# TiltyDuo.net
KiCad netlist of a schematic drawn in EAGLE
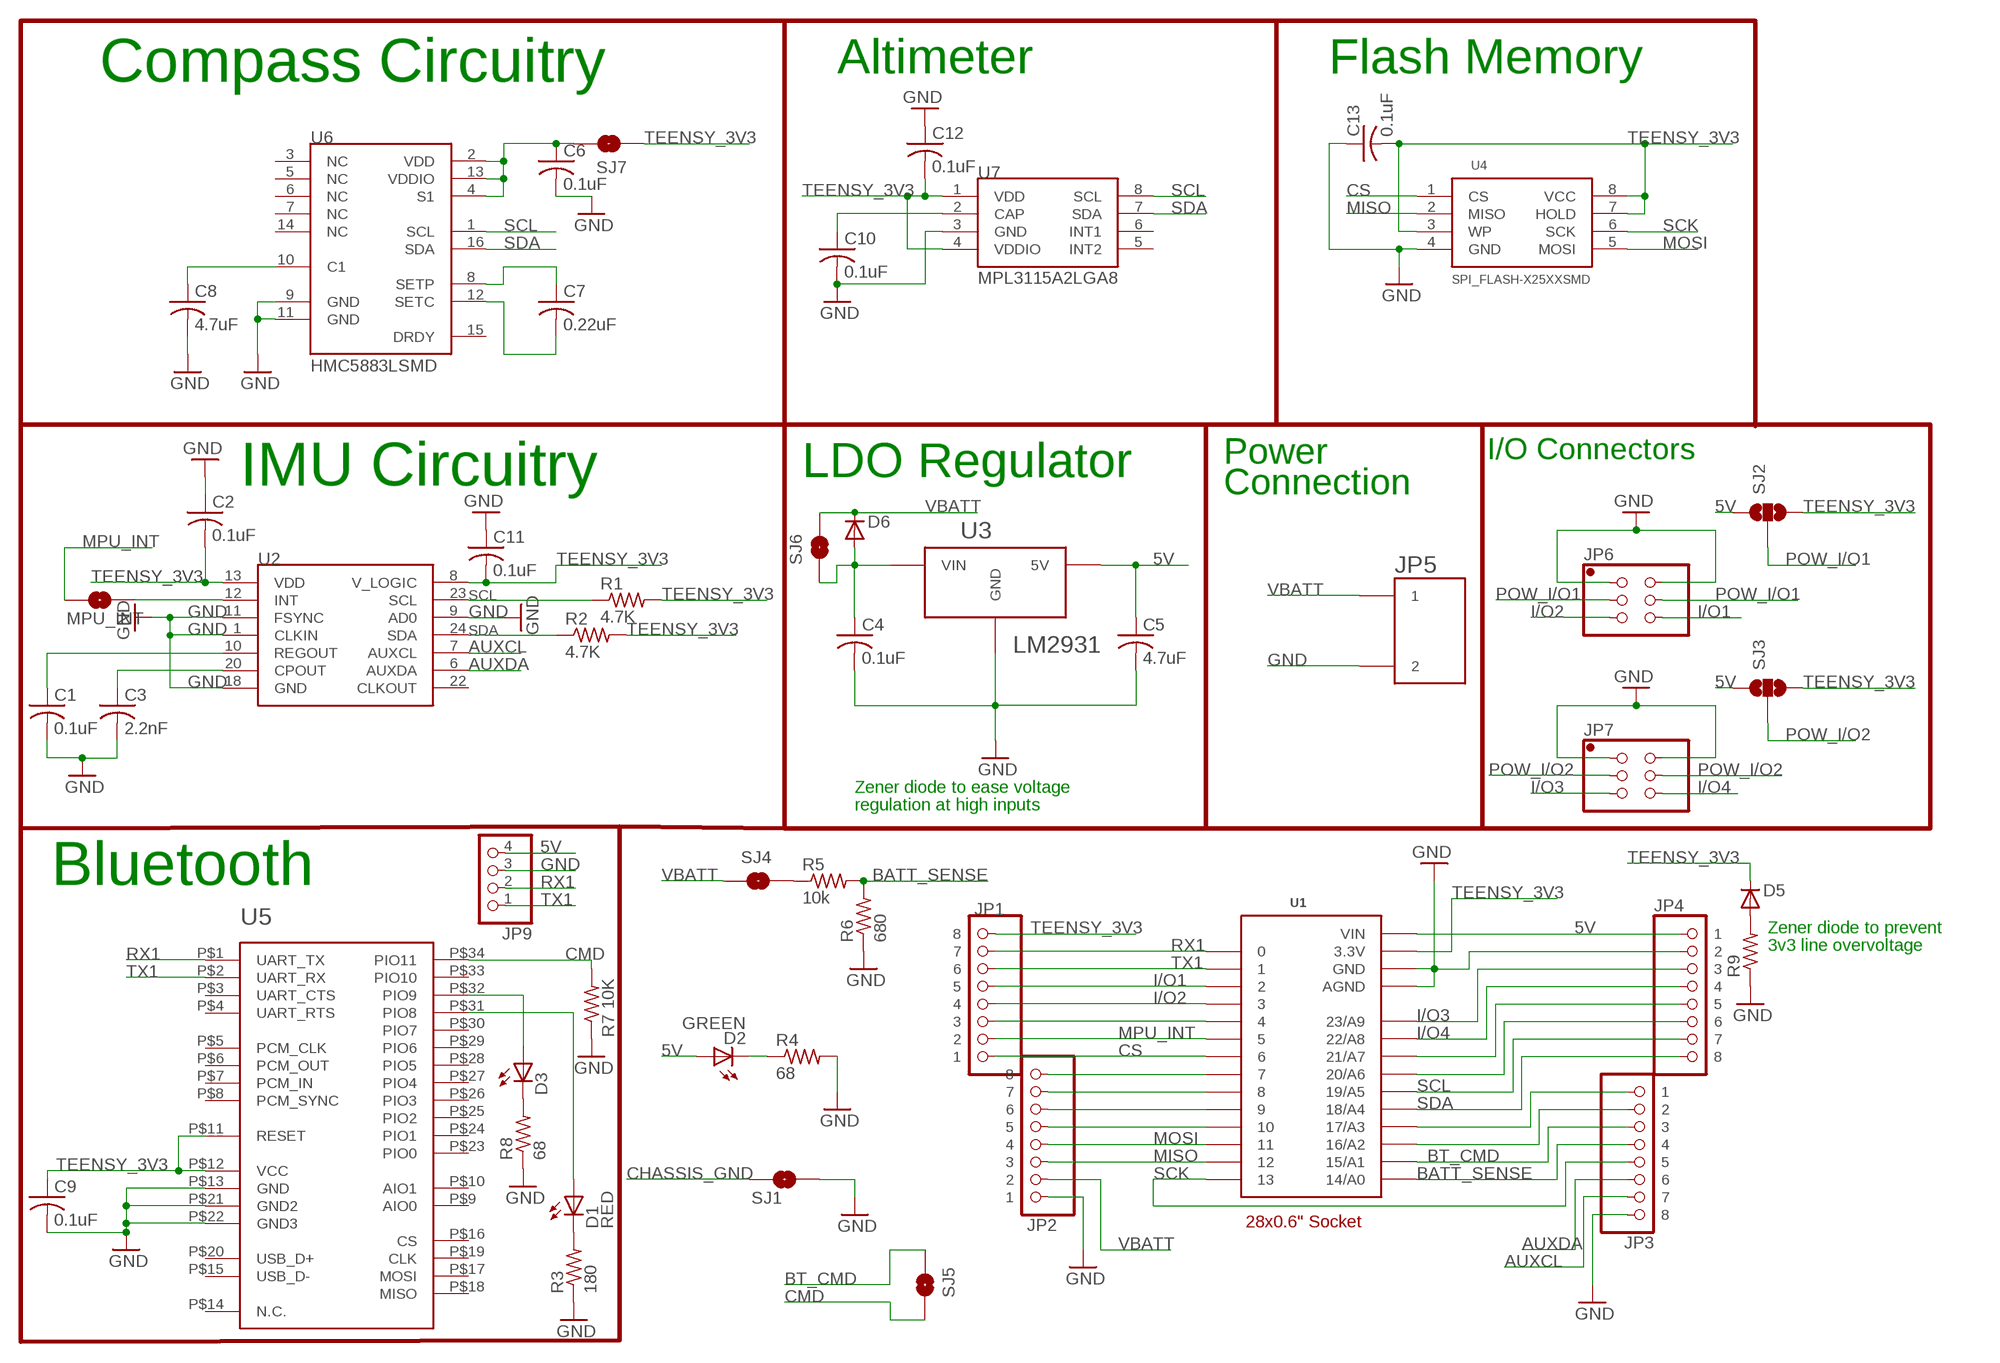
[diagram p0: schematic, sheet 1]

(export (version "E")
  (design (tool "Eeschema 10.0.6"))
  (components
    (comp (ref "C1")
      (value "0.1uF")
      (footprint "eagle-import:C0603")
      (libsource (lib "eagle-import") (part "C-USC0603"))
    )
    (comp (ref "C2")
      (value "0.1uF")
      (footprint "eagle-import:C0603")
      (libsource (lib "eagle-import") (part "C-USC0603"))
    )
    (comp (ref "C3")
      (value "2.2nF")
      (footprint "eagle-import:C0603")
      (libsource (lib "eagle-import") (part "C-USC0603"))
    )
    (comp (ref "C4")
      (value "0.1uF")
      (footprint "eagle-import:C0603")
      (libsource (lib "eagle-import") (part "C-USC0603"))
    )
    (comp (ref "C5")
      (value "4.7uF")
      (footprint "eagle-import:C0603")
      (libsource (lib "eagle-import") (part "C-USC0603"))
    )
    (comp (ref "C6")
      (value "0.1uF")
      (footprint "eagle-import:C0603")
      (libsource (lib "eagle-import") (part "C-USC0603"))
    )
    (comp (ref "C7")
      (value "0.22uF")
      (footprint "eagle-import:C0603")
      (libsource (lib "eagle-import") (part "C-USC0603"))
    )
    (comp (ref "C8")
      (value "4.7uF")
      (footprint "eagle-import:C0603")
      (libsource (lib "eagle-import") (part "C-USC0603"))
    )
    (comp (ref "C9")
      (value "0.1uF")
      (footprint "eagle-import:C0603")
      (libsource (lib "eagle-import") (part "C-USC0603"))
    )
    (comp (ref "C10")
      (value "0.1uF")
      (footprint "eagle-import:C0603")
      (libsource (lib "eagle-import") (part "C-USC0603"))
    )
    (comp (ref "C11")
      (value "0.1uF")
      (footprint "eagle-import:C0603")
      (libsource (lib "eagle-import") (part "C-USC0603"))
    )
    (comp (ref "C12")
      (value "0.1uF")
      (footprint "eagle-import:C0603")
      (libsource (lib "eagle-import") (part "C-USC0603"))
    )
    (comp (ref "C13")
      (value "0.1uF")
      (footprint "eagle-import:C0603")
      (libsource (lib "eagle-import") (part "C-USC0603"))
    )
    (comp (ref "D1")
      (value "RED")
      (footprint "eagle-import:LED-0805")
      (libsource (lib "eagle-import") (part "LED-GREENLED-0805_NO_SILK"))
    )
    (comp (ref "D2")
      (value "GREEN")
      (footprint "eagle-import:LED-0805")
      (libsource (lib "eagle-import") (part "LED-GREENLED-0805_NO_SILK"))
    )
    (comp (ref "D3")
      (value "YELLOW")
      (footprint "eagle-import:LED-0805")
      (libsource (lib "eagle-import") (part "LED-GREENLED-0805_NO_SILK"))
    )
    (comp (ref "D5")
      (value "DIODESOT23")
      (footprint "eagle-import:SOT23-3")
      (fields (field (name "PART#") "BZX84C3V3LT1GOSCT-ND"))
      (libsource (lib "eagle-import") (part "DIODESOT23"))
    )
    (comp (ref "D6")
      (value "DIODE-DO214AA")
      (footprint "eagle-import:DO214AA")
      (libsource (lib "eagle-import") (part "DIODE-DO214AA"))
    )
    (comp (ref "JP1")
      (value "8-PIN_HEADER")
      (footprint "eagle-import:8-PIN_RECEPTACLE_LOCK_NO-SS")
      (libsource (lib "eagle-import") (part "8-PIN_HEADER"))
    )
    (comp (ref "JP2")
      (value "8-PIN_HEADER")
      (footprint "eagle-import:8-PIN_RECEPTACLE_LOCK_NO-SS")
      (libsource (lib "eagle-import") (part "8-PIN_HEADER"))
    )
    (comp (ref "JP3")
      (value "8-PIN_HEADER")
      (footprint "eagle-import:8-PIN_RECEPTACLE_LOCK_NO-SS")
      (libsource (lib "eagle-import") (part "8-PIN_HEADER"))
    )
    (comp (ref "JP4")
      (value "8-PIN_HEADER")
      (footprint "eagle-import:8-PIN_RECEPTACLE_LOCK_NO-SS")
      (libsource (lib "eagle-import") (part "8-PIN_HEADER"))
    )
    (comp (ref "JP5")
      (value "2-POS_SMD_TERM_BLOCK")
      (footprint "eagle-import:2-POS_SMD_TERMINAL_BLOCK")
      (fields (field (name "PART#") "277-2337-1-ND"))
      (libsource (lib "eagle-import") (part "2-POS_SMD_TERM_BLOCK"))
    )
    (comp (ref "JP6")
      (value "PINHD-2X32X03_NO_SS_LOCK")
      (footprint "eagle-import:2X03_NO_SS_LOCK")
      (libsource (lib "eagle-import") (part "PINHD-2X32X03_NO_SS_LOCK"))
    )
    (comp (ref "JP7")
      (value "PINHD-2X32X03_NO_SS_LOCK")
      (footprint "eagle-import:2X03_NO_SS_LOCK")
      (libsource (lib "eagle-import") (part "PINHD-2X32X03_NO_SS_LOCK"))
    )
    (comp (ref "JP9")
      (value "PINHD-1X41X04_NO_SS_LOCKING")
      (footprint "eagle-import:1X04_NO_SS_LOCKING")
      (libsource (lib "eagle-import") (part "PINHD-1X41X04_NO_SS_LOCKING"))
    )
    (comp (ref "MPU_INT")
      (value "SOLDERJUMPERNO")
      (footprint "eagle-import:SJ_2S-NO")
      (libsource (lib "eagle-import") (part "SOLDERJUMPERNO"))
    )
    (comp (ref "R1")
      (value "4.7K")
      (footprint "eagle-import:R0603")
      (libsource (lib "eagle-import") (part "R-US_R0603"))
    )
    (comp (ref "R2")
      (value "4.7K")
      (footprint "eagle-import:R0603")
      (libsource (lib "eagle-import") (part "R-US_R0603"))
    )
    (comp (ref "R3")
      (value "180")
      (footprint "eagle-import:R0603")
      (libsource (lib "eagle-import") (part "R-US_R0603"))
    )
    (comp (ref "R4")
      (value "68")
      (footprint "eagle-import:R0603")
      (libsource (lib "eagle-import") (part "R-US_R0603"))
    )
    (comp (ref "R5")
      (value "10k")
      (footprint "eagle-import:R0603")
      (libsource (lib "eagle-import") (part "R-US_R0603"))
    )
    (comp (ref "R6")
      (value "680")
      (footprint "eagle-import:R0603")
      (libsource (lib "eagle-import") (part "R-US_R0603"))
    )
    (comp (ref "R7")
      (value "10K")
      (footprint "eagle-import:R0603")
      (libsource (lib "eagle-import") (part "R-US_R0603"))
    )
    (comp (ref "R8")
      (value "68")
      (footprint "eagle-import:R0603")
      (libsource (lib "eagle-import") (part "R-US_R0603"))
    )
    (comp (ref "R9")
      (value "R-US_R0603")
      (footprint "eagle-import:R0603")
      (libsource (lib "eagle-import") (part "R-US_R0603"))
    )
    (comp (ref "SJ1")
      (value "SOLDERJUMPERNO")
      (footprint "eagle-import:SJ_2S-NO")
      (libsource (lib "eagle-import") (part "SOLDERJUMPERNO"))
    )
    (comp (ref "SJ2")
      (value "SOLDERJUMPER_2WAYPASTE1&2")
      (footprint "eagle-import:SJ_3_PASTE1&2")
      (libsource (lib "eagle-import") (part "SOLDERJUMPER_2WAYPASTE1&2"))
    )
    (comp (ref "SJ3")
      (value "SOLDERJUMPER_2WAYS")
      (footprint "eagle-import:SJ_3")
      (libsource (lib "eagle-import") (part "SOLDERJUMPER_2WAYS"))
    )
    (comp (ref "SJ4")
      (value "SOLDERJUMPERTRACE")
      (footprint "eagle-import:SJ_2S-TRACE")
      (libsource (lib "eagle-import") (part "SOLDERJUMPERTRACE"))
    )
    (comp (ref "SJ5")
      (value "SOLDERJUMPERTRACE")
      (footprint "eagle-import:SJ_2S-TRACE")
      (libsource (lib "eagle-import") (part "SOLDERJUMPERTRACE"))
    )
    (comp (ref "SJ6")
      (value "SOLDERJUMPERTRACE")
      (footprint "eagle-import:SJ_2S-TRACE")
      (libsource (lib "eagle-import") (part "SOLDERJUMPERTRACE"))
    )
    (comp (ref "SJ7")
      (value "SOLDERJUMPERTRACE")
      (footprint "eagle-import:SJ_2S-TRACE")
      (libsource (lib "eagle-import") (part "SOLDERJUMPERTRACE"))
    )
    (comp (ref "U1")
      (value "TEENSY_3.0_OUTER-PINS28-DIP_SOCKET")
      (footprint "eagle-import:28-DIP")
      (fields (field (name "PART#") "AE10004-ND"))
      (libsource (lib "eagle-import") (part "TEENSY_3.0_OUTER-PINS28-DIP_SOCKET"))
    )
    (comp (ref "U2")
      (value "MPU-6050")
      (footprint "eagle-import:QFN-24")
      (libsource (lib "eagle-import") (part "MPU-6050"))
    )
    (comp (ref "U3")
      (value "LM2931")
      (footprint "eagle-import:TO263")
      (libsource (lib "eagle-import") (part "LM2931"))
    )
    (comp (ref "U4")
      (value "SPI_FLASH-X25XXSMD")
      (footprint "eagle-import:SO08")
      (fields (field (name "PART#") "S25FL204K0TMFI043"))
      (libsource (lib "eagle-import") (part "SPI_FLASH-X25XXSMD"))
    )
    (comp (ref "U5")
      (value "HC-09_BREAKOUT")
      (footprint "eagle-import:HC-09_BREAKOUT")
      (libsource (lib "eagle-import") (part "HC-09_BREAKOUT"))
    )
    (comp (ref "U6")
      (value "HMC5883LSMD")
      (footprint "eagle-import:16LPCC")
      (libsource (lib "eagle-import") (part "HMC5883LSMD"))
    )
    (comp (ref "U7")
      (value "MPL3115A2LGA8")
      (footprint "eagle-import:LGA8")
      (libsource (lib "eagle-import") (part "MPL3115A2LGA8"))
    )
  )
  (nets
    (net (code "1") (name "/5V") (class "Default")
      (node (ref "C5") (pin "1") (pinfunction "1_1") (pintype "passive"))
      (node (ref "D2") (pin "1") (pinfunction "A_1") (pintype "passive"))
      (node (ref "JP4") (pin "P$1") (pinfunction "1_P$1") (pintype "passive"))
      (node (ref "JP9") (pin "4") (pinfunction "4_4") (pintype "passive"))
      (node (ref "SJ2") (pin "1") (pinfunction "1_1") (pintype "passive"))
      (node (ref "SJ3") (pin "1") (pinfunction "1_1") (pintype "passive"))
      (node (ref "U1") (pin "P$15") (pinfunction "VIN_P$15") (pintype "power_in"))
      (node (ref "U3") (pin "P$3") (pinfunction "5V_P$3") (pintype "bidirectional"))
    )
    (net (code "2") (name "/AUXCL") (class "Default")
      (node (ref "JP3") (pin "P$7") (pinfunction "7_P$7") (pintype "passive"))
      (node (ref "U2") (pin "7") (pinfunction "AUXCL_7") (pintype "bidirectional"))
    )
    (net (code "3") (name "/AUXDA") (class "Default")
      (node (ref "JP3") (pin "P$6") (pinfunction "6_P$6") (pintype "passive"))
      (node (ref "U2") (pin "6") (pinfunction "AUXDA_6") (pintype "bidirectional"))
    )
    (net (code "4") (name "/BATT_SENSE") (class "Default")
      (node (ref "JP3") (pin "P$4") (pinfunction "4_P$4") (pintype "passive"))
      (node (ref "R5") (pin "2") (pinfunction "2_2") (pintype "passive"))
      (node (ref "R6") (pin "2") (pinfunction "2_2") (pintype "passive"))
      (node (ref "U1") (pin "P$27") (pinfunction "14/A0_P$27") (pintype "bidirectional"))
    )
    (net (code "5") (name "/BT_CMD") (class "Default")
      (node (ref "JP3") (pin "P$3") (pinfunction "3_P$3") (pintype "passive"))
      (node (ref "SJ5") (pin "1") (pinfunction "1_1") (pintype "passive"))
      (node (ref "U1") (pin "P$26") (pinfunction "15/A1_P$26") (pintype "bidirectional"))
    )
    (net (code "6") (name "/CHASSIS_GND") (class "Default")
      (node (ref "SJ1") (pin "1") (pinfunction "1_1") (pintype "passive"))
    )
    (net (code "7") (name "/CMD") (class "Default")
      (node (ref "R7") (pin "2") (pinfunction "2_2") (pintype "passive"))
      (node (ref "SJ5") (pin "2") (pinfunction "2_2") (pintype "passive"))
      (node (ref "U5") (pin "P$34") (pinfunction "PIO11_P$34") (pintype "bidirectional"))
    )
    (net (code "8") (name "/CS") (class "Default")
      (node (ref "JP1") (pin "P$1") (pinfunction "1_P$1") (pintype "passive"))
      (node (ref "U1") (pin "P$8") (pinfunction "6_P$8") (pintype "bidirectional"))
      (node (ref "U4") (pin "1") (pinfunction "CS_1") (pintype "bidirectional"))
    )
    (net (code "9") (name "/I{slash}O1") (class "Default")
      (node (ref "JP1") (pin "P$5") (pinfunction "5_P$5") (pintype "passive"))
      (node (ref "JP6") (pin "6") (pinfunction "6_6") (pintype "passive"))
      (node (ref "U1") (pin "P$4") (pinfunction "2_P$4") (pintype "bidirectional"))
    )
    (net (code "10") (name "/I{slash}O2") (class "Default")
      (node (ref "JP1") (pin "P$4") (pinfunction "4_P$4") (pintype "passive"))
      (node (ref "JP6") (pin "5") (pinfunction "5_5") (pintype "passive"))
      (node (ref "U1") (pin "P$5") (pinfunction "3_P$5") (pintype "bidirectional"))
    )
    (net (code "11") (name "/I{slash}O3") (class "Default")
      (node (ref "JP4") (pin "P$3") (pinfunction "3_P$3") (pintype "passive"))
      (node (ref "JP7") (pin "5") (pinfunction "5_5") (pintype "passive"))
      (node (ref "U1") (pin "P$18") (pinfunction "23/A9_P$18") (pintype "bidirectional"))
    )
    (net (code "12") (name "/I{slash}O4") (class "Default")
      (node (ref "JP4") (pin "P$4") (pinfunction "4_P$4") (pintype "passive"))
      (node (ref "JP7") (pin "6") (pinfunction "6_6") (pintype "passive"))
      (node (ref "U1") (pin "P$19") (pinfunction "22/A8_P$19") (pintype "bidirectional"))
    )
    (net (code "13") (name "/MISO") (class "Default")
      (node (ref "JP2") (pin "P$3") (pinfunction "3_P$3") (pintype "passive"))
      (node (ref "U1") (pin "P$14") (pinfunction "12_P$14") (pintype "bidirectional"))
      (node (ref "U4") (pin "2") (pinfunction "MISO_2") (pintype "bidirectional"))
    )
    (net (code "14") (name "/MOSI") (class "Default")
      (node (ref "JP2") (pin "P$4") (pinfunction "4_P$4") (pintype "passive"))
      (node (ref "U1") (pin "P$13") (pinfunction "11_P$13") (pintype "bidirectional"))
      (node (ref "U4") (pin "5") (pinfunction "MOSI_5") (pintype "bidirectional"))
    )
    (net (code "15") (name "/MPU_INT") (class "Default")
      (node (ref "JP1") (pin "P$2") (pinfunction "2_P$2") (pintype "passive"))
      (node (ref "MPU_INT") (pin "1") (pinfunction "1_1") (pintype "passive"))
      (node (ref "U1") (pin "P$7") (pinfunction "5_P$7") (pintype "bidirectional"))
    )
    (net (code "16") (name "/POW_I{slash}O1") (class "Default")
      (node (ref "JP6") (pin "3") (pinfunction "3_3") (pintype "passive"))
      (node (ref "JP6") (pin "4") (pinfunction "4_4") (pintype "passive"))
      (node (ref "SJ2") (pin "2") (pinfunction "2_2") (pintype "passive"))
    )
    (net (code "17") (name "/POW_I{slash}O2") (class "Default")
      (node (ref "JP7") (pin "3") (pinfunction "3_3") (pintype "passive"))
      (node (ref "JP7") (pin "4") (pinfunction "4_4") (pintype "passive"))
      (node (ref "SJ3") (pin "2") (pinfunction "2_2") (pintype "passive"))
    )
    (net (code "18") (name "/RX1") (class "Default")
      (node (ref "JP1") (pin "P$7") (pinfunction "7_P$7") (pintype "passive"))
      (node (ref "JP9") (pin "2") (pinfunction "2_2") (pintype "passive"))
      (node (ref "U1") (pin "P$2") (pinfunction "0_P$2") (pintype "bidirectional"))
      (node (ref "U5") (pin "P$1") (pinfunction "UART_TX_P$1") (pintype "bidirectional"))
    )
    (net (code "19") (name "/SCK") (class "Default")
      (node (ref "JP3") (pin "P$5") (pinfunction "5_P$5") (pintype "passive"))
      (node (ref "U1") (pin "P$28") (pinfunction "13_P$28") (pintype "bidirectional"))
      (node (ref "U4") (pin "6") (pinfunction "SCK_6") (pintype "bidirectional"))
    )
    (net (code "20") (name "/SCL") (class "Default")
      (node (ref "JP4") (pin "P$7") (pinfunction "7_P$7") (pintype "passive"))
      (node (ref "R1") (pin "1") (pinfunction "1_1") (pintype "passive"))
      (node (ref "U1") (pin "P$22") (pinfunction "19/A5_P$22") (pintype "bidirectional"))
      (node (ref "U2") (pin "23") (pinfunction "SCL_23") (pintype "bidirectional"))
      (node (ref "U6") (pin "1") (pinfunction "SCL_1") (pintype "bidirectional"))
      (node (ref "U7") (pin "8") (pinfunction "SCL_8") (pintype "bidirectional"))
    )
    (net (code "21") (name "/SDA") (class "Default")
      (node (ref "JP4") (pin "P$8") (pinfunction "8_P$8") (pintype "passive"))
      (node (ref "R2") (pin "1") (pinfunction "1_1") (pintype "passive"))
      (node (ref "U1") (pin "P$23") (pinfunction "18/A4_P$23") (pintype "bidirectional"))
      (node (ref "U2") (pin "24") (pinfunction "SDA_24") (pintype "bidirectional"))
      (node (ref "U6") (pin "16") (pinfunction "SDA_16") (pintype "bidirectional"))
      (node (ref "U7") (pin "7") (pinfunction "SDA_7") (pintype "bidirectional"))
    )
    (net (code "22") (name "/TEENSY_3V3") (class "Default")
      (node (ref "C11") (pin "2") (pinfunction "2_2") (pintype "passive"))
      (node (ref "C12") (pin "2") (pinfunction "2_2") (pintype "passive"))
      (node (ref "C13") (pin "2") (pinfunction "2_2") (pintype "passive"))
      (node (ref "C2") (pin "2") (pinfunction "2_2") (pintype "passive"))
      (node (ref "C9") (pin "1") (pinfunction "1_1") (pintype "passive"))
      (node (ref "D5") (pin "3") (pinfunction "C_3") (pintype "passive"))
      (node (ref "JP1") (pin "P$8") (pinfunction "8_P$8") (pintype "passive"))
      (node (ref "R1") (pin "2") (pinfunction "2_2") (pintype "passive"))
      (node (ref "R2") (pin "2") (pinfunction "2_2") (pintype "passive"))
      (node (ref "SJ2") (pin "3") (pinfunction "3_3") (pintype "passive"))
      (node (ref "SJ3") (pin "3") (pinfunction "3_3") (pintype "passive"))
      (node (ref "SJ7") (pin "1") (pinfunction "1_1") (pintype "passive"))
      (node (ref "U1") (pin "P$17") (pinfunction "3.3V_P$17") (pintype "power_in"))
      (node (ref "U2") (pin "13") (pinfunction "VDD_13") (pintype "bidirectional"))
      (node (ref "U2") (pin "8") (pinfunction "V_LOGIC_8") (pintype "bidirectional"))
      (node (ref "U4") (pin "3") (pinfunction "WP_3") (pintype "bidirectional"))
      (node (ref "U4") (pin "7") (pinfunction "HOLD_7") (pintype "bidirectional"))
      (node (ref "U4") (pin "8") (pinfunction "VCC_8") (pintype "bidirectional"))
      (node (ref "U5") (pin "P$11") (pinfunction "RESET_P$11") (pintype "bidirectional"))
      (node (ref "U5") (pin "P$12") (pinfunction "VCC_P$12") (pintype "bidirectional"))
      (node (ref "U7") (pin "1") (pinfunction "VDD_1") (pintype "bidirectional"))
      (node (ref "U7") (pin "4") (pinfunction "VDDIO_4") (pintype "bidirectional"))
    )
    (net (code "23") (name "/TX1") (class "Default")
      (node (ref "JP1") (pin "P$6") (pinfunction "6_P$6") (pintype "passive"))
      (node (ref "JP9") (pin "1") (pinfunction "1_1") (pintype "passive"))
      (node (ref "U1") (pin "P$3") (pinfunction "1_P$3") (pintype "bidirectional"))
      (node (ref "U5") (pin "P$2") (pinfunction "UART_RX_P$2") (pintype "bidirectional"))
    )
    (net (code "24") (name "/VBATT") (class "Default")
      (node (ref "C4") (pin "1") (pinfunction "1_1") (pintype "passive"))
      (node (ref "D6") (pin "A") (pinfunction "A_A") (pintype "passive"))
      (node (ref "D6") (pin "C") (pinfunction "C_C") (pintype "passive"))
      (node (ref "JP2") (pin "P$2") (pinfunction "2_P$2") (pintype "passive"))
      (node (ref "JP5") (pin "P$3") (pinfunction "1_P$3") (pintype "bidirectional"))
      (node (ref "SJ4") (pin "1") (pinfunction "1_1") (pintype "passive"))
      (node (ref "SJ6") (pin "1") (pinfunction "1_1") (pintype "passive"))
      (node (ref "SJ6") (pin "2") (pinfunction "2_2") (pintype "passive"))
      (node (ref "U3") (pin "P$2") (pinfunction "VIN_P$2") (pintype "bidirectional"))
    )
    (net (code "25") (name "GND") (class "Default")
      (node (ref "C1") (pin "2") (pinfunction "2_2") (pintype "passive"))
      (node (ref "C10") (pin "2") (pinfunction "2_2") (pintype "passive"))
      (node (ref "C11") (pin "1") (pinfunction "1_1") (pintype "passive"))
      (node (ref "C12") (pin "1") (pinfunction "1_1") (pintype "passive"))
      (node (ref "C13") (pin "1") (pinfunction "1_1") (pintype "passive"))
      (node (ref "C2") (pin "1") (pinfunction "1_1") (pintype "passive"))
      (node (ref "C3") (pin "2") (pinfunction "2_2") (pintype "passive"))
      (node (ref "C4") (pin "2") (pinfunction "2_2") (pintype "passive"))
      (node (ref "C5") (pin "2") (pinfunction "2_2") (pintype "passive"))
      (node (ref "C6") (pin "2") (pinfunction "2_2") (pintype "passive"))
      (node (ref "C8") (pin "2") (pinfunction "2_2") (pintype "passive"))
      (node (ref "C9") (pin "2") (pinfunction "2_2") (pintype "passive"))
      (node (ref "JP2") (pin "P$1") (pinfunction "1_P$1") (pintype "passive"))
      (node (ref "JP3") (pin "P$8") (pinfunction "8_P$8") (pintype "passive"))
      (node (ref "JP4") (pin "P$2") (pinfunction "2_P$2") (pintype "passive"))
      (node (ref "JP5") (pin "P$4") (pinfunction "2_P$4") (pintype "bidirectional"))
      (node (ref "JP6") (pin "1") (pinfunction "1_1") (pintype "passive"))
      (node (ref "JP6") (pin "2") (pinfunction "2_2") (pintype "passive"))
      (node (ref "JP7") (pin "1") (pinfunction "1_1") (pintype "passive"))
      (node (ref "JP7") (pin "2") (pinfunction "2_2") (pintype "passive"))
      (node (ref "JP9") (pin "3") (pinfunction "3_3") (pintype "passive"))
      (node (ref "R3") (pin "1") (pinfunction "1_1") (pintype "passive"))
      (node (ref "R4") (pin "2") (pinfunction "2_2") (pintype "passive"))
      (node (ref "R6") (pin "1") (pinfunction "1_1") (pintype "passive"))
      (node (ref "R7") (pin "1") (pinfunction "1_1") (pintype "passive"))
      (node (ref "R8") (pin "1") (pinfunction "1_1") (pintype "passive"))
      (node (ref "R9") (pin "1") (pinfunction "1_1") (pintype "passive"))
      (node (ref "SJ1") (pin "2") (pinfunction "2_2") (pintype "passive"))
      (node (ref "U1") (pin "P$1") (pinfunction "GND_P$1") (pintype "power_in"))
      (node (ref "U1") (pin "P$16") (pinfunction "AGND_P$16") (pintype "power_in"))
      (node (ref "U2") (pin "1") (pinfunction "CLKIN_1") (pintype "bidirectional"))
      (node (ref "U2") (pin "11") (pinfunction "FSYNC_11") (pintype "bidirectional"))
      (node (ref "U2") (pin "18") (pinfunction "GND_18") (pintype "bidirectional"))
      (node (ref "U2") (pin "9") (pinfunction "AD0_9") (pintype "bidirectional"))
      (node (ref "U3") (pin "P$1") (pinfunction "GND_P$1") (pintype "bidirectional"))
      (node (ref "U4") (pin "4") (pinfunction "GND_4") (pintype "bidirectional"))
      (node (ref "U5") (pin "P$13") (pinfunction "GND_P$13") (pintype "bidirectional"))
      (node (ref "U5") (pin "P$21") (pinfunction "GND2_P$21") (pintype "bidirectional"))
      (node (ref "U5") (pin "P$22") (pinfunction "GND3_P$22") (pintype "bidirectional"))
      (node (ref "U6") (pin "11") (pinfunction "GND_11") (pintype "bidirectional"))
      (node (ref "U6") (pin "9") (pinfunction "GND_9") (pintype "bidirectional"))
      (node (ref "U7") (pin "3") (pinfunction "GND_3") (pintype "bidirectional"))
    )
    (net (code "26") (name "Net-(D1-A)") (class "Default")
      (node (ref "D1") (pin "1") (pinfunction "A_1") (pintype "passive"))
      (node (ref "U5") (pin "P$31") (pinfunction "PIO8_P$31") (pintype "bidirectional"))
    )
    (net (code "27") (name "Net-(D1-C)") (class "Default")
      (node (ref "D1") (pin "2") (pinfunction "C_2") (pintype "passive"))
      (node (ref "R3") (pin "2") (pinfunction "2_2") (pintype "passive"))
    )
    (net (code "28") (name "Net-(D2-C)") (class "Default")
      (node (ref "D2") (pin "2") (pinfunction "C_2") (pintype "passive"))
      (node (ref "R4") (pin "1") (pinfunction "1_1") (pintype "passive"))
    )
    (net (code "29") (name "Net-(D3-A)") (class "Default")
      (node (ref "D3") (pin "1") (pinfunction "A_1") (pintype "passive"))
      (node (ref "U5") (pin "P$32") (pinfunction "PIO9_P$32") (pintype "bidirectional"))
    )
    (net (code "30") (name "Net-(D3-C)") (class "Default")
      (node (ref "D3") (pin "2") (pinfunction "C_2") (pintype "passive"))
      (node (ref "R8") (pin "2") (pinfunction "2_2") (pintype "passive"))
    )
    (net (code "31") (name "Net-(D5-A)") (class "Default")
      (node (ref "D5") (pin "1") (pinfunction "A_1") (pintype "passive"))
      (node (ref "R9") (pin "2") (pinfunction "2_2") (pintype "passive"))
    )
    (net (code "32") (name "Net-(JP1-3)") (class "Default")
      (node (ref "JP1") (pin "P$3") (pinfunction "3_P$3") (pintype "passive"))
      (node (ref "U1") (pin "P$6") (pinfunction "4_P$6") (pintype "bidirectional"))
    )
    (net (code "33") (name "Net-(JP2-5)") (class "Default")
      (node (ref "JP2") (pin "P$5") (pinfunction "5_P$5") (pintype "passive"))
      (node (ref "U1") (pin "P$12") (pinfunction "10_P$12") (pintype "bidirectional"))
    )
    (net (code "34") (name "Net-(JP2-6)") (class "Default")
      (node (ref "JP2") (pin "P$6") (pinfunction "6_P$6") (pintype "passive"))
      (node (ref "U1") (pin "P$11") (pinfunction "9_P$11") (pintype "bidirectional"))
    )
    (net (code "35") (name "Net-(JP2-7)") (class "Default")
      (node (ref "JP2") (pin "P$7") (pinfunction "7_P$7") (pintype "passive"))
      (node (ref "U1") (pin "P$10") (pinfunction "8_P$10") (pintype "bidirectional"))
    )
    (net (code "36") (name "Net-(JP2-8)") (class "Default")
      (node (ref "JP2") (pin "P$8") (pinfunction "8_P$8") (pintype "passive"))
      (node (ref "U1") (pin "P$9") (pinfunction "7_P$9") (pintype "bidirectional"))
    )
    (net (code "37") (name "Net-(JP3-1)") (class "Default")
      (node (ref "JP3") (pin "P$1") (pinfunction "1_P$1") (pintype "passive"))
      (node (ref "U1") (pin "P$24") (pinfunction "17/A3_P$24") (pintype "bidirectional"))
    )
    (net (code "38") (name "Net-(JP3-2)") (class "Default")
      (node (ref "JP3") (pin "P$2") (pinfunction "2_P$2") (pintype "passive"))
      (node (ref "U1") (pin "P$25") (pinfunction "16/A2_P$25") (pintype "bidirectional"))
    )
    (net (code "39") (name "Net-(JP4-5)") (class "Default")
      (node (ref "JP4") (pin "P$5") (pinfunction "5_P$5") (pintype "passive"))
      (node (ref "U1") (pin "P$20") (pinfunction "21/A7_P$20") (pintype "bidirectional"))
    )
    (net (code "40") (name "Net-(JP4-6)") (class "Default")
      (node (ref "JP4") (pin "P$6") (pinfunction "6_P$6") (pintype "passive"))
      (node (ref "U1") (pin "P$21") (pinfunction "20/A6_P$21") (pintype "bidirectional"))
    )
    (net (code "41") (name "Net-(R5-Pad1)") (class "Default")
      (node (ref "R5") (pin "1") (pinfunction "1_1") (pintype "passive"))
      (node (ref "SJ4") (pin "2") (pinfunction "2_2") (pintype "passive"))
    )
    (net (code "42") (name "Net-(U2-CPOUT)") (class "Default")
      (node (ref "C3") (pin "1") (pinfunction "1_1") (pintype "passive"))
      (node (ref "U2") (pin "20") (pinfunction "CPOUT_20") (pintype "bidirectional"))
    )
    (net (code "43") (name "Net-(U2-INT)") (class "Default")
      (node (ref "MPU_INT") (pin "2") (pinfunction "2_2") (pintype "passive"))
      (node (ref "U2") (pin "12") (pinfunction "INT_12") (pintype "bidirectional"))
    )
    (net (code "44") (name "Net-(U2-REGOUT)") (class "Default")
      (node (ref "C1") (pin "1") (pinfunction "1_1") (pintype "passive"))
      (node (ref "U2") (pin "10") (pinfunction "REGOUT_10") (pintype "bidirectional"))
    )
    (net (code "45") (name "Net-(U6-C1)") (class "Default")
      (node (ref "C8") (pin "1") (pinfunction "1_1") (pintype "passive"))
      (node (ref "U6") (pin "10") (pinfunction "C1_10") (pintype "bidirectional"))
    )
    (net (code "46") (name "Net-(U6-S1)") (class "Default")
      (node (ref "C6") (pin "1") (pinfunction "1_1") (pintype "passive"))
      (node (ref "SJ7") (pin "2") (pinfunction "2_2") (pintype "passive"))
      (node (ref "U6") (pin "13") (pinfunction "VDDIO_13") (pintype "bidirectional"))
      (node (ref "U6") (pin "2") (pinfunction "VDD_2") (pintype "bidirectional"))
      (node (ref "U6") (pin "4") (pinfunction "S1_4") (pintype "bidirectional"))
    )
    (net (code "47") (name "Net-(U6-SETC)") (class "Default")
      (node (ref "C7") (pin "2") (pinfunction "2_2") (pintype "passive"))
      (node (ref "U6") (pin "12") (pinfunction "SETC_12") (pintype "bidirectional"))
    )
    (net (code "48") (name "Net-(U6-SETP)") (class "Default")
      (node (ref "C7") (pin "1") (pinfunction "1_1") (pintype "passive"))
      (node (ref "U6") (pin "8") (pinfunction "SETP_8") (pintype "bidirectional"))
    )
    (net (code "49") (name "Net-(U7-CAP)") (class "Default")
      (node (ref "C10") (pin "1") (pinfunction "1_1") (pintype "passive"))
      (node (ref "U7") (pin "2") (pinfunction "CAP_2") (pintype "bidirectional"))
    )
    (net (code "50") (name "unconnected-(U2-CLKOUT-Pad22)") (class "Default")
      (node (ref "U2") (pin "22") (pinfunction "CLKOUT_22") (pintype "bidirectional"))
    )
    (net (code "51") (name "unconnected-(U5-AIO0-PadP$9)") (class "Default")
      (node (ref "U5") (pin "P$9") (pinfunction "AIO0_P$9") (pintype "bidirectional"))
    )
    (net (code "52") (name "unconnected-(U5-AIO1-PadP$10)") (class "Default")
      (node (ref "U5") (pin "P$10") (pinfunction "AIO1_P$10") (pintype "bidirectional"))
    )
    (net (code "53") (name "unconnected-(U5-CLK-PadP$19)") (class "Default")
      (node (ref "U5") (pin "P$19") (pinfunction "CLK_P$19") (pintype "bidirectional"))
    )
    (net (code "54") (name "unconnected-(U5-CS-PadP$16)") (class "Default")
      (node (ref "U5") (pin "P$16") (pinfunction "CS_P$16") (pintype "bidirectional"))
    )
    (net (code "55") (name "unconnected-(U5-MISO-PadP$18)") (class "Default")
      (node (ref "U5") (pin "P$18") (pinfunction "MISO_P$18") (pintype "bidirectional"))
    )
    (net (code "56") (name "unconnected-(U5-MOSI-PadP$17)") (class "Default")
      (node (ref "U5") (pin "P$17") (pinfunction "MOSI_P$17") (pintype "bidirectional"))
    )
    (net (code "57") (name "unconnected-(U5-N.C.-PadP$14)") (class "Default")
      (node (ref "U5") (pin "P$14") (pinfunction "N.C._P$14") (pintype "bidirectional"))
    )
    (net (code "58") (name "unconnected-(U5-PCM_CLK-PadP$5)") (class "Default")
      (node (ref "U5") (pin "P$5") (pinfunction "PCM_CLK_P$5") (pintype "bidirectional"))
    )
    (net (code "59") (name "unconnected-(U5-PCM_IN-PadP$7)") (class "Default")
      (node (ref "U5") (pin "P$7") (pinfunction "PCM_IN_P$7") (pintype "bidirectional"))
    )
    (net (code "60") (name "unconnected-(U5-PCM_OUT-PadP$6)") (class "Default")
      (node (ref "U5") (pin "P$6") (pinfunction "PCM_OUT_P$6") (pintype "bidirectional"))
    )
    (net (code "61") (name "unconnected-(U5-PCM_SYNC-PadP$8)") (class "Default")
      (node (ref "U5") (pin "P$8") (pinfunction "PCM_SYNC_P$8") (pintype "bidirectional"))
    )
    (net (code "62") (name "unconnected-(U5-PIO0-PadP$23)") (class "Default")
      (node (ref "U5") (pin "P$23") (pinfunction "PIO0_P$23") (pintype "bidirectional"))
    )
    (net (code "63") (name "unconnected-(U5-PIO1-PadP$24)") (class "Default")
      (node (ref "U5") (pin "P$24") (pinfunction "PIO1_P$24") (pintype "bidirectional"))
    )
    (net (code "64") (name "unconnected-(U5-PIO2-PadP$25)") (class "Default")
      (node (ref "U5") (pin "P$25") (pinfunction "PIO2_P$25") (pintype "bidirectional"))
    )
    (net (code "65") (name "unconnected-(U5-PIO3-PadP$26)") (class "Default")
      (node (ref "U5") (pin "P$26") (pinfunction "PIO3_P$26") (pintype "bidirectional"))
    )
    (net (code "66") (name "unconnected-(U5-PIO4-PadP$27)") (class "Default")
      (node (ref "U5") (pin "P$27") (pinfunction "PIO4_P$27") (pintype "bidirectional"))
    )
    (net (code "67") (name "unconnected-(U5-PIO5-PadP$28)") (class "Default")
      (node (ref "U5") (pin "P$28") (pinfunction "PIO5_P$28") (pintype "bidirectional"))
    )
    (net (code "68") (name "unconnected-(U5-PIO6-PadP$29)") (class "Default")
      (node (ref "U5") (pin "P$29") (pinfunction "PIO6_P$29") (pintype "bidirectional"))
    )
    (net (code "69") (name "unconnected-(U5-PIO7-PadP$30)") (class "Default")
      (node (ref "U5") (pin "P$30") (pinfunction "PIO7_P$30") (pintype "bidirectional"))
    )
    (net (code "70") (name "unconnected-(U5-PIO10-PadP$33)") (class "Default")
      (node (ref "U5") (pin "P$33") (pinfunction "PIO10_P$33") (pintype "bidirectional"))
    )
    (net (code "71") (name "unconnected-(U5-UART_CTS-PadP$3)") (class "Default")
      (node (ref "U5") (pin "P$3") (pinfunction "UART_CTS_P$3") (pintype "bidirectional"))
    )
    (net (code "72") (name "unconnected-(U5-UART_RTS-PadP$4)") (class "Default")
      (node (ref "U5") (pin "P$4") (pinfunction "UART_RTS_P$4") (pintype "bidirectional"))
    )
    (net (code "73") (name "unconnected-(U5-USB_D+-PadP$20)") (class "Default")
      (node (ref "U5") (pin "P$20") (pinfunction "USB_D+_P$20") (pintype "bidirectional"))
    )
    (net (code "74") (name "unconnected-(U5-USB_D--PadP$15)") (class "Default")
      (node (ref "U5") (pin "P$15") (pinfunction "USB_D-_P$15") (pintype "bidirectional"))
    )
    (net (code "75") (name "unconnected-(U6-DRDY-Pad15)") (class "Default")
      (node (ref "U6") (pin "15") (pinfunction "DRDY_15") (pintype "bidirectional"))
    )
    (net (code "76") (name "unconnected-(U6-NC-Pad3)") (class "Default")
      (node (ref "U6") (pin "3") (pinfunction "NC_3") (pintype "bidirectional"))
    )
    (net (code "77") (name "unconnected-(U6-NC-Pad5)") (class "Default")
      (node (ref "U6") (pin "5") (pinfunction "NC_5") (pintype "bidirectional"))
    )
    (net (code "78") (name "unconnected-(U6-NC-Pad6)") (class "Default")
      (node (ref "U6") (pin "6") (pinfunction "NC_6") (pintype "bidirectional"))
    )
    (net (code "79") (name "unconnected-(U6-NC-Pad7)") (class "Default")
      (node (ref "U6") (pin "7") (pinfunction "NC_7") (pintype "bidirectional"))
    )
    (net (code "80") (name "unconnected-(U6-NC-Pad14)") (class "Default")
      (node (ref "U6") (pin "14") (pinfunction "NC_14") (pintype "bidirectional"))
    )
    (net (code "81") (name "unconnected-(U7-INT1-Pad6)") (class "Default")
      (node (ref "U7") (pin "6") (pinfunction "INT1_6") (pintype "bidirectional"))
    )
    (net (code "82") (name "unconnected-(U7-INT2-Pad5)") (class "Default")
      (node (ref "U7") (pin "5") (pinfunction "INT2_5") (pintype "bidirectional"))
    )
  )
)
